# Extension_Knocklet.net
KiCad netlist of a schematic drawn in Altium Designer
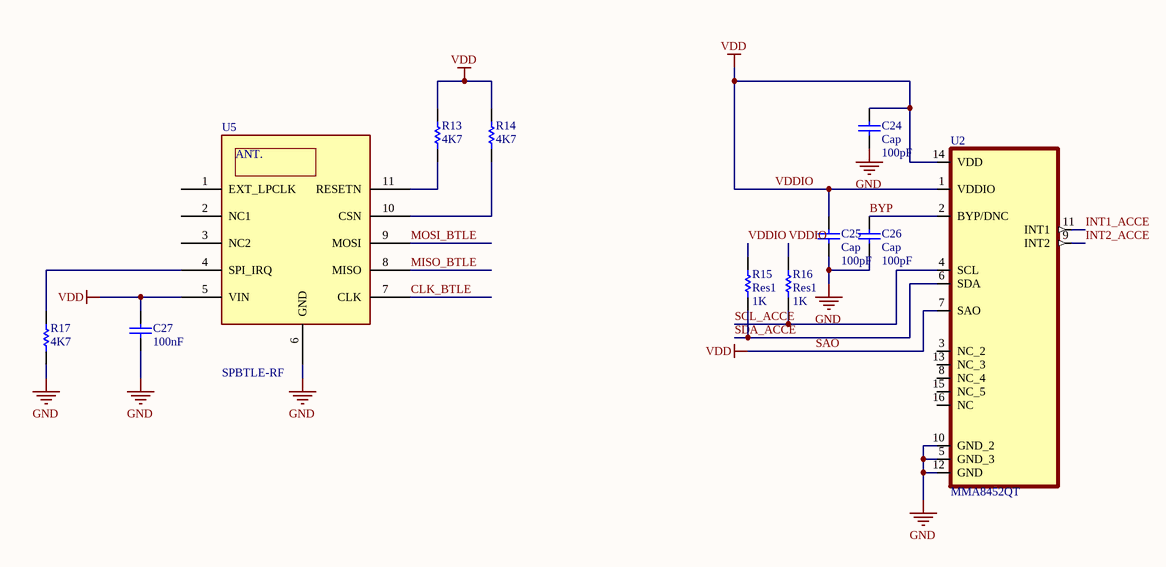
[diagram p0: Extension Knocklet.SchDoc]

(export (version "E")
  (design (tool "Eeschema 10.0.6"))
  (components
    (comp (ref "C24")
      (value "Cap")
      (footprint "RAD-0.3")
      (description "Capacitor")
      (fields (field (name "ALTIUM_VALUE") "100pF") (field (name "PUBLISHER") "Altium Limited"))
      (libsource (lib "Miscellaneous Devices") (part "Cap"))
    )
    (comp (ref "C25")
      (value "Cap")
      (footprint "RAD-0.3")
      (description "Capacitor")
      (fields (field (name "ALTIUM_VALUE") "100pF") (field (name "PUBLISHER") "Altium Limited"))
      (libsource (lib "Miscellaneous Devices") (part "Cap"))
    )
    (comp (ref "C26")
      (value "Cap")
      (footprint "RAD-0.3")
      (description "Capacitor")
      (fields (field (name "ALTIUM_VALUE") "100pF") (field (name "PUBLISHER") "Altium Limited"))
      (libsource (lib "Miscellaneous Devices") (part "Cap"))
    )
    (comp (ref "C27")
      (value "100nF")
      (footprint "0603")
      (description "Capacitor")
      (fields (field (name "PUBLISHER") "Altium Limited"))
      (libsource (lib "KNOCKLET_BRAC") (part "Cap"))
    )
    (comp (ref "R13")
      (value "4K7")
      (footprint "0402R")
      (description "Resistor")
      (fields (field (name "PUBLISHER") "Altium Limited"))
      (libsource (lib "KNOCKLET_BRAC") (part "Res1"))
    )
    (comp (ref "R14")
      (value "4K7")
      (footprint "0402R")
      (description "Resistor")
      (fields (field (name "PUBLISHER") "Altium Limited"))
      (libsource (lib "KNOCKLET_BRAC") (part "Res1"))
    )
    (comp (ref "R15")
      (value "Res1")
      (footprint "AXIAL-0.3")
      (description "Resistor")
      (fields (field (name "ALTIUM_VALUE") "1K") (field (name "PUBLISHER") "Altium Limited"))
      (libsource (lib "Miscellaneous Devices") (part "Res1"))
    )
    (comp (ref "R16")
      (value "Res1")
      (footprint "AXIAL-0.3")
      (description "Resistor")
      (fields (field (name "ALTIUM_VALUE") "1K") (field (name "PUBLISHER") "Altium Limited"))
      (libsource (lib "Miscellaneous Devices") (part "Res1"))
    )
    (comp (ref "R17")
      (value "4K7")
      (footprint "0402R")
      (description "Resistor")
      (fields (field (name "PUBLISHER") "Altium Limited"))
      (libsource (lib "KNOCKLET_BRAC") (part "Res1"))
    )
    (comp (ref "U2")
      (value "MMA8452QT")
      (footprint "MMA8452QT")
      (libsource (lib "Accelerometres") (part "MMA8452QT"))
    )
    (comp (ref "U5")
      (value "SPBTLE-RF")
      (footprint "SPBTLE-RF")
      (description "Module BlueNRG")
      (libsource (lib "KNOCKLET_BRAC") (part "SPBTLE-RF"))
    )
  )
  (nets
    (net (code "1") (name "/BYP") (class "Default")
      (node (ref "C26") (pin "2") (pinfunction "2_2") (pintype "passive"))
      (node (ref "U2") (pin "2") (pinfunction "BYP/DNC_2") (pintype "passive"))
    )
    (net (code "2") (name "/CLK_BTLE") (class "Default")
      (node (ref "U5") (pin "7") (pinfunction "CLK_7") (pintype "passive"))
    )
    (net (code "3") (name "/INT1_ACCE") (class "Default")
      (node (ref "U2") (pin "11") (pinfunction "INT1_11") (pintype "output"))
    )
    (net (code "4") (name "/INT2_ACCE") (class "Default")
      (node (ref "U2") (pin "9") (pinfunction "INT2_9") (pintype "output"))
    )
    (net (code "5") (name "/MISO_BTLE") (class "Default")
      (node (ref "U5") (pin "8") (pinfunction "MISO_8") (pintype "passive"))
    )
    (net (code "6") (name "/MOSI_BTLE") (class "Default")
      (node (ref "U5") (pin "9") (pinfunction "MOSI_9") (pintype "passive"))
    )
    (net (code "7") (name "/SCL_ACCE") (class "Default")
      (node (ref "R16") (pin "1") (pinfunction "1_1") (pintype "passive"))
      (node (ref "U2") (pin "4") (pinfunction "SCL_4") (pintype "passive"))
    )
    (net (code "8") (name "/SDA_ACCE") (class "Default")
      (node (ref "R15") (pin "1") (pinfunction "1_1") (pintype "passive"))
      (node (ref "U2") (pin "6") (pinfunction "SDA_6") (pintype "passive"))
    )
    (net (code "9") (name "GND") (class "Default")
      (node (ref "C24") (pin "1") (pinfunction "1_1") (pintype "passive"))
      (node (ref "C25") (pin "1") (pinfunction "1_1") (pintype "passive"))
      (node (ref "C26") (pin "1") (pinfunction "1_1") (pintype "passive"))
      (node (ref "C27") (pin "1") (pinfunction "1_1") (pintype "passive"))
      (node (ref "R17") (pin "2") (pinfunction "2_2") (pintype "passive"))
      (node (ref "U2") (pin "10") (pinfunction "GND_2_10") (pintype "passive"))
      (node (ref "U2") (pin "12") (pinfunction "GND_12") (pintype "passive"))
      (node (ref "U2") (pin "5") (pinfunction "GND_3_5") (pintype "passive"))
      (node (ref "U5") (pin "6") (pinfunction "GND_6") (pintype "passive"))
    )
    (net (code "10") (name "Net-(U5-CSN)") (class "Default")
      (node (ref "R14") (pin "2") (pinfunction "2_2") (pintype "passive"))
      (node (ref "U5") (pin "10") (pinfunction "CSN_10") (pintype "passive"))
    )
    (net (code "11") (name "Net-(U5-RESETN)") (class "Default")
      (node (ref "R13") (pin "2") (pinfunction "2_2") (pintype "passive"))
      (node (ref "U5") (pin "11") (pinfunction "RESETN_11") (pintype "passive"))
    )
    (net (code "12") (name "Net-(U5-SPI_IRQ)") (class "Default")
      (node (ref "R17") (pin "1") (pinfunction "1_1") (pintype "passive"))
      (node (ref "U5") (pin "4") (pinfunction "SPI_IRQ_4") (pintype "passive"))
    )
    (net (code "13") (name "VDD") (class "Default")
      (node (ref "C24") (pin "2") (pinfunction "2_2") (pintype "passive"))
      (node (ref "C25") (pin "2") (pinfunction "2_2") (pintype "passive"))
      (node (ref "C27") (pin "2") (pinfunction "2_2") (pintype "passive"))
      (node (ref "R13") (pin "1") (pinfunction "1_1") (pintype "passive"))
      (node (ref "R14") (pin "1") (pinfunction "1_1") (pintype "passive"))
      (node (ref "R15") (pin "2") (pinfunction "2_2") (pintype "passive"))
      (node (ref "R16") (pin "2") (pinfunction "2_2") (pintype "passive"))
      (node (ref "U2") (pin "1") (pinfunction "VDDIO_1") (pintype "power_in"))
      (node (ref "U2") (pin "14") (pinfunction "VDD_14") (pintype "power_in"))
      (node (ref "U2") (pin "7") (pinfunction "SAO_7") (pintype "passive"))
      (node (ref "U5") (pin "5") (pinfunction "VIN_5") (pintype "passive"))
    )
    (net (code "14") (name "unconnected-(U2-NC-Pad16)") (class "Default")
      (node (ref "U2") (pin "16") (pinfunction "NC_16") (pintype "passive"))
    )
    (net (code "15") (name "unconnected-(U2-NC_2-Pad3)") (class "Default")
      (node (ref "U2") (pin "3") (pinfunction "NC_2_3") (pintype "passive"))
    )
    (net (code "16") (name "unconnected-(U2-NC_3-Pad13)") (class "Default")
      (node (ref "U2") (pin "13") (pinfunction "NC_3_13") (pintype "passive"))
    )
    (net (code "17") (name "unconnected-(U2-NC_4-Pad8)") (class "Default")
      (node (ref "U2") (pin "8") (pinfunction "NC_4_8") (pintype "passive"))
    )
    (net (code "18") (name "unconnected-(U2-NC_5-Pad15)") (class "Default")
      (node (ref "U2") (pin "15") (pinfunction "NC_5_15") (pintype "passive"))
    )
    (net (code "19") (name "unconnected-(U5-EXT_LPCLK-Pad1)") (class "Default")
      (node (ref "U5") (pin "1") (pinfunction "EXT_LPCLK_1") (pintype "passive"))
    )
    (net (code "20") (name "unconnected-(U5-NC1-Pad2)") (class "Default")
      (node (ref "U5") (pin "2") (pinfunction "NC1_2") (pintype "passive"))
    )
    (net (code "21") (name "unconnected-(U5-NC2-Pad3)") (class "Default")
      (node (ref "U5") (pin "3") (pinfunction "NC2_3") (pintype "passive"))
    )
  )
)
